# 362MiniProj.net
KiCad netlist of a schematic drawn in EAGLE
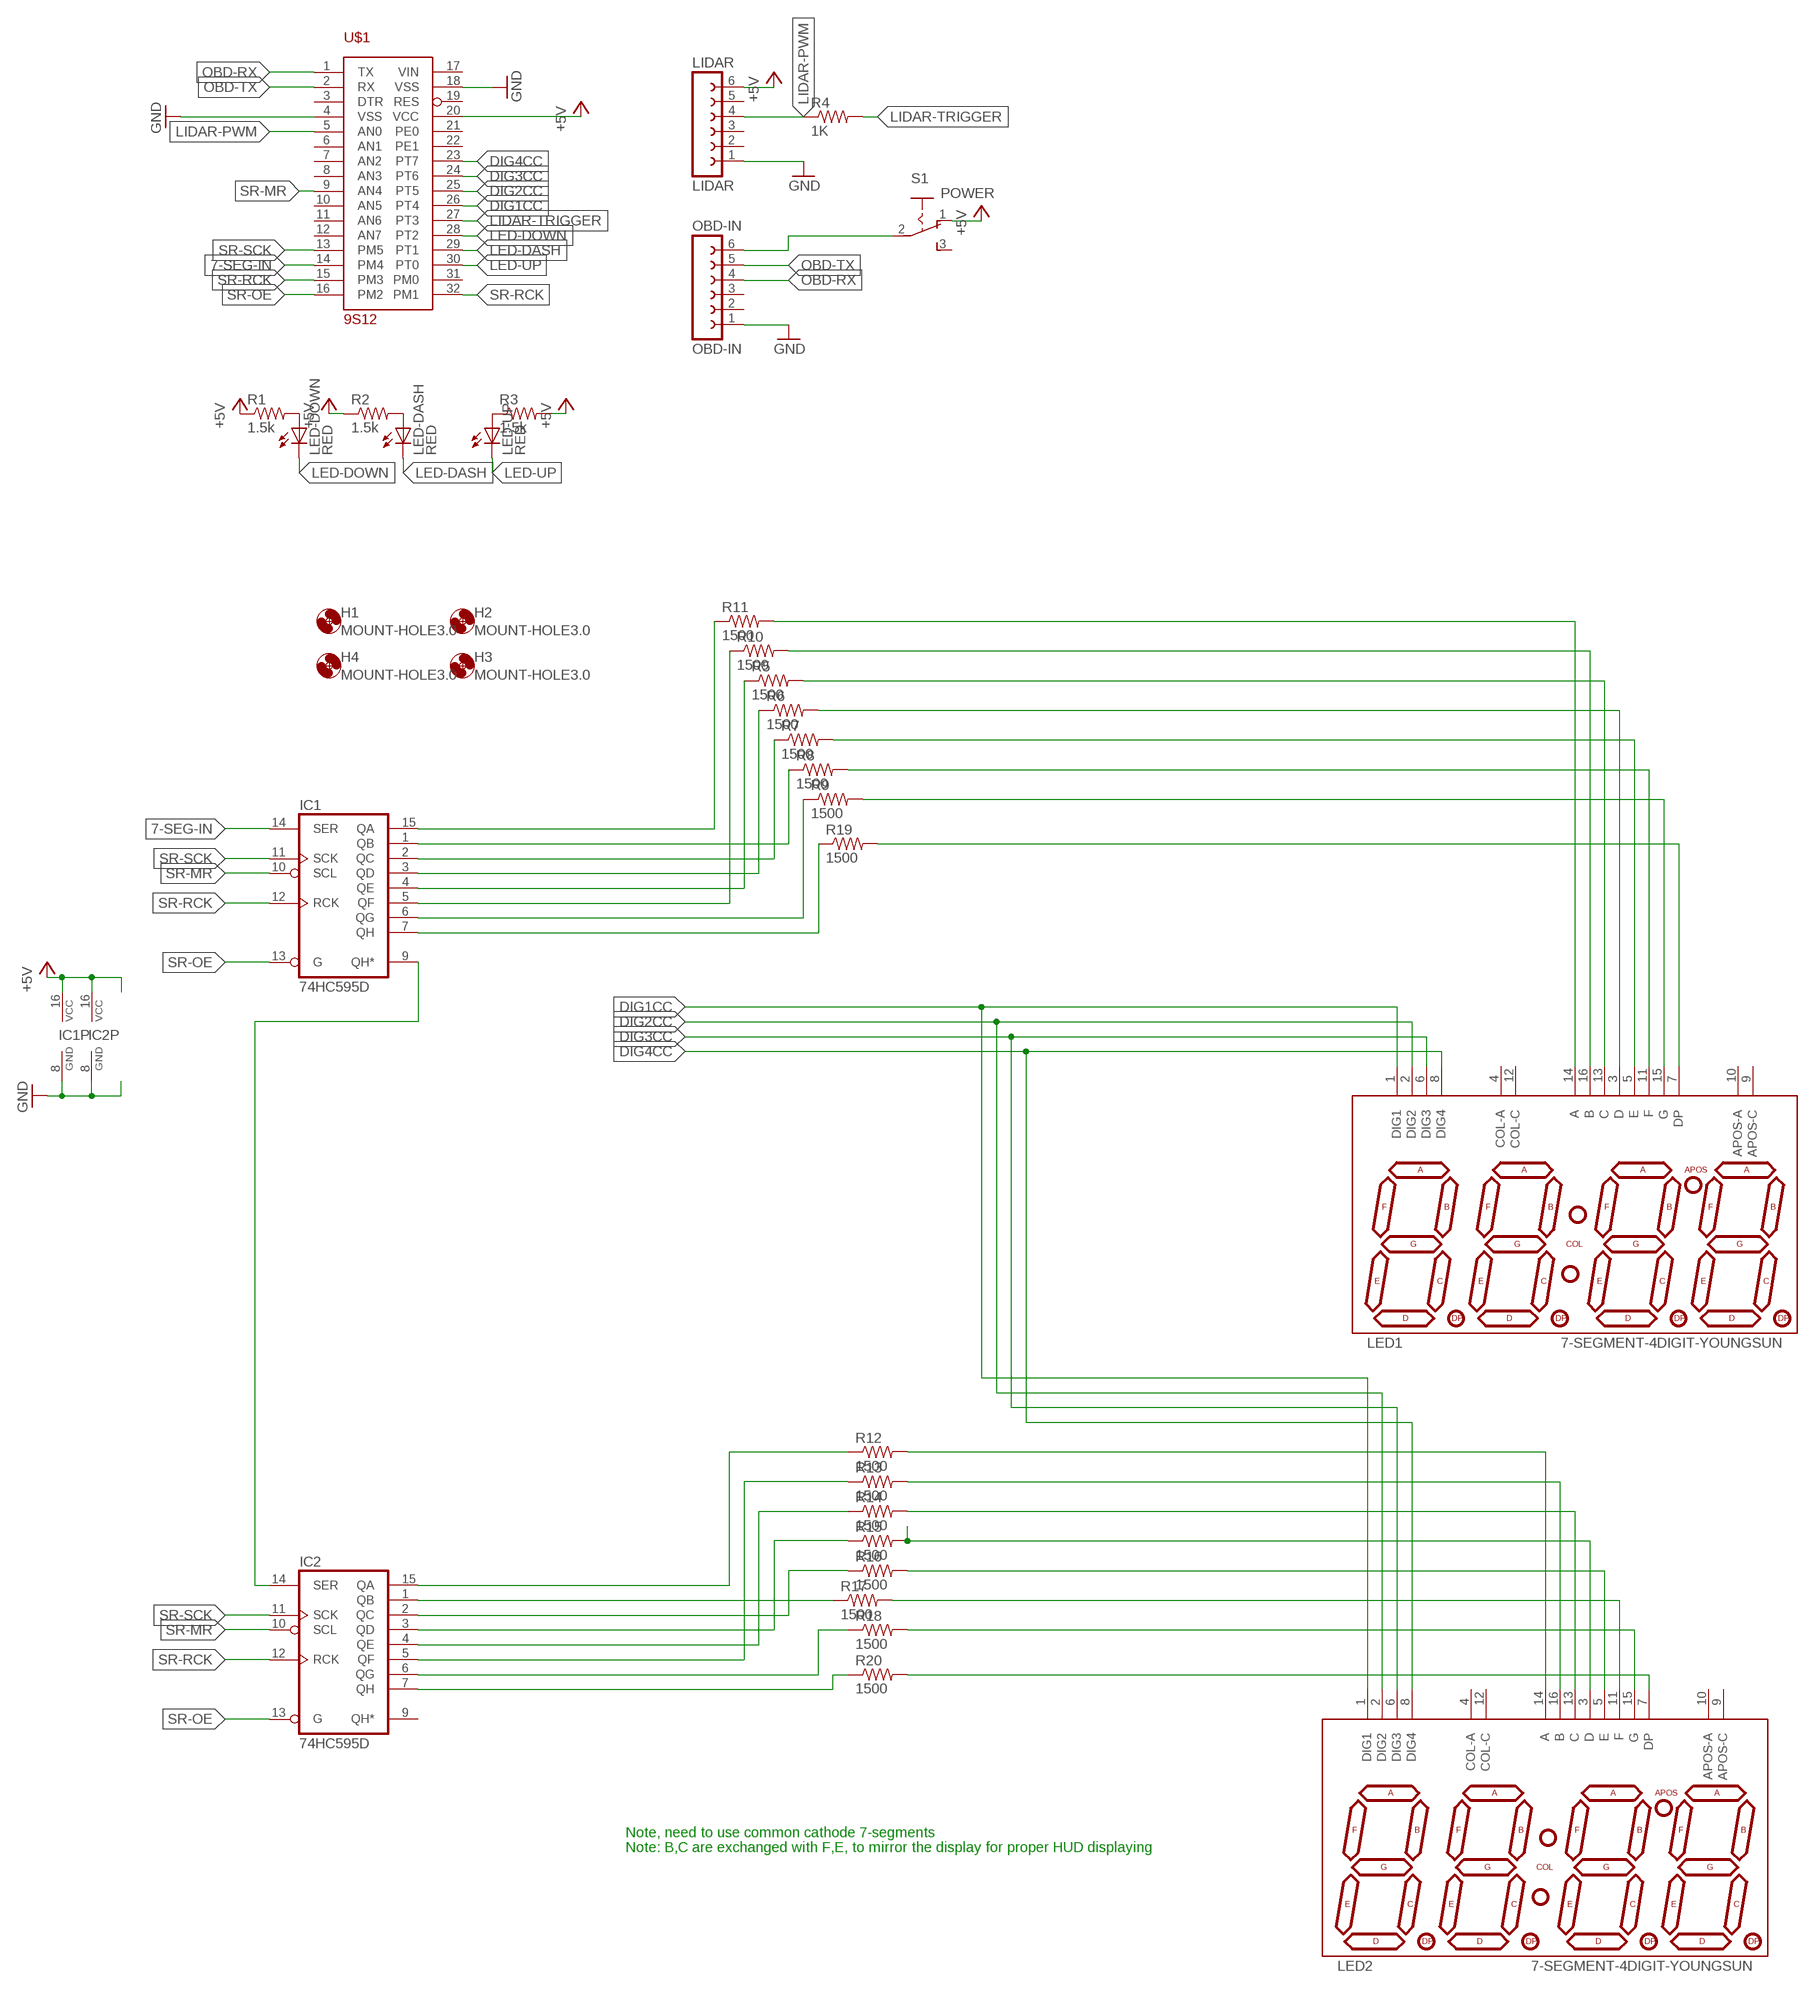
[diagram p0: schematic, sheet 1]

(export (version "E")
  (design (tool "Eeschema 10.0.6"))
  (components
    (comp (ref "H1")
      (value "MOUNT-HOLE3.0")
      (footprint "eagle-import:3,0")
      (libsource (lib "eagle-import") (part "MOUNT-HOLE3.0"))
    )
    (comp (ref "H2")
      (value "MOUNT-HOLE3.0")
      (footprint "eagle-import:3,0")
      (libsource (lib "eagle-import") (part "MOUNT-HOLE3.0"))
    )
    (comp (ref "H3")
      (value "MOUNT-HOLE3.0")
      (footprint "eagle-import:3,0")
      (libsource (lib "eagle-import") (part "MOUNT-HOLE3.0"))
    )
    (comp (ref "H4")
      (value "MOUNT-HOLE3.0")
      (footprint "eagle-import:3,0")
      (libsource (lib "eagle-import") (part "MOUNT-HOLE3.0"))
    )
    (comp (ref "IC1")
      (value "74HC595D")
      (footprint "eagle-import:SO16")
      (libsource (lib "eagle-import") (part "74595DHC"))
    )
    (comp (ref "IC2")
      (value "74HC595D")
      (footprint "eagle-import:SO16")
      (libsource (lib "eagle-import") (part "74595DHC"))
    )
    (comp (ref "LED-DASH")
      (value "RED")
      (footprint "eagle-import:LED_1206")
      (libsource (lib "eagle-import") (part "LED_E"))
    )
    (comp (ref "LED-DOWN")
      (value "RED")
      (footprint "eagle-import:LED_1206")
      (libsource (lib "eagle-import") (part "LED_E"))
    )
    (comp (ref "LED-UP")
      (value "RED")
      (footprint "eagle-import:LED_1206")
      (libsource (lib "eagle-import") (part "LED_E"))
    )
    (comp (ref "LED1")
      (value "7-SEGMENT-4DIGIT-YOUNGSUN")
      (footprint "eagle-import:7-SEGMENT-4DIGIT-YOUNGSUN")
      (libsource (lib "eagle-import") (part "7-SEGMENT-4DIGIT-YOUNGSUN"))
    )
    (comp (ref "LED2")
      (value "7-SEGMENT-4DIGIT-YOUNGSUN")
      (footprint "eagle-import:7-SEGMENT-4DIGIT-YOUNGSUN")
      (libsource (lib "eagle-import") (part "7-SEGMENT-4DIGIT-YOUNGSUN"))
    )
    (comp (ref "LIDAR")
      (value "LIDAR")
      (footprint "eagle-import:FE06")
      (libsource (lib "eagle-import") (part "FE06-1"))
    )
    (comp (ref "OBD-IN")
      (value "OBD-IN")
      (footprint "eagle-import:FE06")
      (libsource (lib "eagle-import") (part "FE06-1"))
    )
    (comp (ref "R1")
      (value "1.5k")
      (footprint "eagle-import:M1206")
      (libsource (lib "eagle-import") (part "R-US_M1206"))
    )
    (comp (ref "R2")
      (value "1.5k")
      (footprint "eagle-import:M1206")
      (libsource (lib "eagle-import") (part "R-US_M1206"))
    )
    (comp (ref "R3")
      (value "1.5k")
      (footprint "eagle-import:M1206")
      (libsource (lib "eagle-import") (part "R-US_M1206"))
    )
    (comp (ref "R4")
      (value "1K")
      (footprint "eagle-import:M1206")
      (libsource (lib "eagle-import") (part "R-US_M1206"))
    )
    (comp (ref "R5")
      (value "1500")
      (footprint "eagle-import:M1206")
      (libsource (lib "eagle-import") (part "R-US_M1206"))
    )
    (comp (ref "R6")
      (value "1500")
      (footprint "eagle-import:M1206")
      (libsource (lib "eagle-import") (part "R-US_M1206"))
    )
    (comp (ref "R7")
      (value "1500")
      (footprint "eagle-import:M1206")
      (libsource (lib "eagle-import") (part "R-US_M1206"))
    )
    (comp (ref "R8")
      (value "1500")
      (footprint "eagle-import:M1206")
      (libsource (lib "eagle-import") (part "R-US_M1206"))
    )
    (comp (ref "R9")
      (value "1500")
      (footprint "eagle-import:M1206")
      (libsource (lib "eagle-import") (part "R-US_M1206"))
    )
    (comp (ref "R10")
      (value "1500")
      (footprint "eagle-import:M1206")
      (libsource (lib "eagle-import") (part "R-US_M1206"))
    )
    (comp (ref "R11")
      (value "1500")
      (footprint "eagle-import:M1206")
      (libsource (lib "eagle-import") (part "R-US_M1206"))
    )
    (comp (ref "R12")
      (value "1500")
      (footprint "eagle-import:M1206")
      (libsource (lib "eagle-import") (part "R-US_M1206"))
    )
    (comp (ref "R13")
      (value "1500")
      (footprint "eagle-import:M1206")
      (libsource (lib "eagle-import") (part "R-US_M1206"))
    )
    (comp (ref "R14")
      (value "1500")
      (footprint "eagle-import:M1206")
      (libsource (lib "eagle-import") (part "R-US_M1206"))
    )
    (comp (ref "R15")
      (value "1500")
      (footprint "eagle-import:M1206")
      (libsource (lib "eagle-import") (part "R-US_M1206"))
    )
    (comp (ref "R16")
      (value "1500")
      (footprint "eagle-import:M1206")
      (libsource (lib "eagle-import") (part "R-US_M1206"))
    )
    (comp (ref "R17")
      (value "1500")
      (footprint "eagle-import:M1206")
      (libsource (lib "eagle-import") (part "R-US_M1206"))
    )
    (comp (ref "R18")
      (value "1500")
      (footprint "eagle-import:M1206")
      (libsource (lib "eagle-import") (part "R-US_M1206"))
    )
    (comp (ref "R19")
      (value "1500")
      (footprint "eagle-import:M1206")
      (libsource (lib "eagle-import") (part "R-US_M1206"))
    )
    (comp (ref "R20")
      (value "1500")
      (footprint "eagle-import:M1206")
      (libsource (lib "eagle-import") (part "R-US_M1206"))
    )
    (comp (ref "S1")
      (value "POWER")
      (footprint "eagle-import:M251")
      (libsource (lib "eagle-import") (part "M251"))
    )
    (comp (ref "U$1")
      (value "9S12")
      (footprint "eagle-import:DIP-32")
      (libsource (lib "eagle-import") (part "9S12"))
    )
  )
  (nets
    (net (code "1") (name "+5V") (class "Default")
      (node (ref "IC1") (pin "16") (pinfunction "VCC_16") (pintype "power_in"))
      (node (ref "IC2") (pin "16") (pinfunction "VCC_16") (pintype "power_in"))
      (node (ref "LIDAR") (pin "6") (pinfunction "6_6") (pintype "passive"))
      (node (ref "R1") (pin "1") (pinfunction "1_1") (pintype "passive"))
      (node (ref "R2") (pin "1") (pinfunction "1_1") (pintype "passive"))
      (node (ref "R3") (pin "2") (pinfunction "2_2") (pintype "passive"))
      (node (ref "S1") (pin "1") (pinfunction "O_1") (pintype "passive"))
      (node (ref "U$1") (pin "20") (pinfunction "VCC_20") (pintype "bidirectional"))
    )
    (net (code "2") (name "7-SEG-IN") (class "Default")
      (node (ref "IC1") (pin "14") (pinfunction "SER_14") (pintype "input"))
      (node (ref "U$1") (pin "14") (pinfunction "PM4_14") (pintype "bidirectional"))
    )
    (net (code "3") (name "DIG1CC") (class "Default")
      (node (ref "LED1") (pin "1") (pinfunction "DIG1_1") (pintype "bidirectional"))
      (node (ref "LED2") (pin "1") (pinfunction "DIG1_1") (pintype "bidirectional"))
      (node (ref "U$1") (pin "26") (pinfunction "PT4_26") (pintype "bidirectional"))
    )
    (net (code "4") (name "DIG2CC") (class "Default")
      (node (ref "LED1") (pin "2") (pinfunction "DIG2_2") (pintype "bidirectional"))
      (node (ref "LED2") (pin "2") (pinfunction "DIG2_2") (pintype "bidirectional"))
      (node (ref "U$1") (pin "25") (pinfunction "PT5_25") (pintype "bidirectional"))
    )
    (net (code "5") (name "DIG3CC") (class "Default")
      (node (ref "LED1") (pin "6") (pinfunction "DIG3_6") (pintype "bidirectional"))
      (node (ref "LED2") (pin "6") (pinfunction "DIG3_6") (pintype "bidirectional"))
      (node (ref "U$1") (pin "24") (pinfunction "PT6_24") (pintype "bidirectional"))
    )
    (net (code "6") (name "DIG4CC") (class "Default")
      (node (ref "LED1") (pin "8") (pinfunction "DIG4_8") (pintype "bidirectional"))
      (node (ref "LED2") (pin "8") (pinfunction "DIG4_8") (pintype "bidirectional"))
      (node (ref "U$1") (pin "23") (pinfunction "PT7_23") (pintype "bidirectional"))
    )
    (net (code "7") (name "GND") (class "Default")
      (node (ref "IC1") (pin "8") (pinfunction "GND_8") (pintype "power_in"))
      (node (ref "IC2") (pin "8") (pinfunction "GND_8") (pintype "power_in"))
      (node (ref "LIDAR") (pin "1") (pinfunction "1_1") (pintype "passive"))
      (node (ref "OBD-IN") (pin "1") (pinfunction "1_1") (pintype "passive"))
      (node (ref "U$1") (pin "18") (pinfunction "VSS_18") (pintype "bidirectional"))
      (node (ref "U$1") (pin "4") (pinfunction "VSS_4") (pintype "bidirectional"))
    )
    (net (code "8") (name "LED-DASH") (class "Default")
      (node (ref "LED-DASH") (pin "C") (pinfunction "C_C") (pintype "passive"))
      (node (ref "U$1") (pin "29") (pinfunction "PT1_29") (pintype "bidirectional"))
    )
    (net (code "9") (name "LED-DOWN") (class "Default")
      (node (ref "LED-DOWN") (pin "C") (pinfunction "C_C") (pintype "passive"))
      (node (ref "U$1") (pin "28") (pinfunction "PT2_28") (pintype "bidirectional"))
    )
    (net (code "10") (name "LED-UP") (class "Default")
      (node (ref "LED-UP") (pin "C") (pinfunction "C_C") (pintype "passive"))
      (node (ref "U$1") (pin "30") (pinfunction "PT0_30") (pintype "bidirectional"))
    )
    (net (code "11") (name "LIDAR-PWM") (class "Default")
      (node (ref "LIDAR") (pin "4") (pinfunction "4_4") (pintype "passive"))
      (node (ref "R4") (pin "1") (pinfunction "1_1") (pintype "passive"))
      (node (ref "U$1") (pin "5") (pinfunction "AN0_5") (pintype "bidirectional"))
    )
    (net (code "12") (name "LIDAR-TRIGGER") (class "Default")
      (node (ref "R4") (pin "2") (pinfunction "2_2") (pintype "passive"))
      (node (ref "U$1") (pin "27") (pinfunction "PT3_27") (pintype "bidirectional"))
    )
    (net (code "13") (name "Net-(IC1A-QA)") (class "Default")
      (node (ref "IC1") (pin "15") (pinfunction "QA_15") (pintype "tri_state"))
      (node (ref "R11") (pin "1") (pinfunction "1_1") (pintype "passive"))
    )
    (net (code "14") (name "Net-(IC1A-QB)") (class "Default")
      (node (ref "IC1") (pin "1") (pinfunction "QB_1") (pintype "tri_state"))
      (node (ref "R8") (pin "1") (pinfunction "1_1") (pintype "passive"))
    )
    (net (code "15") (name "Net-(IC1A-QC)") (class "Default")
      (node (ref "IC1") (pin "2") (pinfunction "QC_2") (pintype "tri_state"))
      (node (ref "R7") (pin "1") (pinfunction "1_1") (pintype "passive"))
    )
    (net (code "16") (name "Net-(IC1A-QD)") (class "Default")
      (node (ref "IC1") (pin "3") (pinfunction "QD_3") (pintype "tri_state"))
      (node (ref "R6") (pin "1") (pinfunction "1_1") (pintype "passive"))
    )
    (net (code "17") (name "Net-(IC1A-QE)") (class "Default")
      (node (ref "IC1") (pin "4") (pinfunction "QE_4") (pintype "tri_state"))
      (node (ref "R5") (pin "1") (pinfunction "1_1") (pintype "passive"))
    )
    (net (code "18") (name "Net-(IC1A-QF)") (class "Default")
      (node (ref "IC1") (pin "5") (pinfunction "QF_5") (pintype "tri_state"))
      (node (ref "R10") (pin "1") (pinfunction "1_1") (pintype "passive"))
    )
    (net (code "19") (name "Net-(IC1A-QG)") (class "Default")
      (node (ref "IC1") (pin "6") (pinfunction "QG_6") (pintype "tri_state"))
      (node (ref "R9") (pin "1") (pinfunction "1_1") (pintype "passive"))
    )
    (net (code "20") (name "Net-(IC1A-QH)") (class "Default")
      (node (ref "IC1") (pin "7") (pinfunction "QH_7") (pintype "tri_state"))
      (node (ref "R19") (pin "1") (pinfunction "1_1") (pintype "passive"))
    )
    (net (code "21") (name "Net-(IC1A-QH*)") (class "Default")
      (node (ref "IC1") (pin "9") (pinfunction "QH*_9") (pintype "tri_state"))
      (node (ref "IC2") (pin "14") (pinfunction "SER_14") (pintype "input"))
    )
    (net (code "22") (name "Net-(IC2A-QA)") (class "Default")
      (node (ref "IC2") (pin "15") (pinfunction "QA_15") (pintype "tri_state"))
      (node (ref "R12") (pin "1") (pinfunction "1_1") (pintype "passive"))
    )
    (net (code "23") (name "Net-(IC2A-QB)") (class "Default")
      (node (ref "IC2") (pin "1") (pinfunction "QB_1") (pintype "tri_state"))
      (node (ref "R17") (pin "1") (pinfunction "1_1") (pintype "passive"))
    )
    (net (code "24") (name "Net-(IC2A-QC)") (class "Default")
      (node (ref "IC2") (pin "2") (pinfunction "QC_2") (pintype "tri_state"))
      (node (ref "R16") (pin "1") (pinfunction "1_1") (pintype "passive"))
    )
    (net (code "25") (name "Net-(IC2A-QD)") (class "Default")
      (node (ref "IC2") (pin "3") (pinfunction "QD_3") (pintype "tri_state"))
      (node (ref "R15") (pin "1") (pinfunction "1_1") (pintype "passive"))
    )
    (net (code "26") (name "Net-(IC2A-QE)") (class "Default")
      (node (ref "IC2") (pin "4") (pinfunction "QE_4") (pintype "tri_state"))
      (node (ref "R14") (pin "1") (pinfunction "1_1") (pintype "passive"))
    )
    (net (code "27") (name "Net-(IC2A-QF)") (class "Default")
      (node (ref "IC2") (pin "5") (pinfunction "QF_5") (pintype "tri_state"))
      (node (ref "R13") (pin "1") (pinfunction "1_1") (pintype "passive"))
    )
    (net (code "28") (name "Net-(IC2A-QG)") (class "Default")
      (node (ref "IC2") (pin "6") (pinfunction "QG_6") (pintype "tri_state"))
      (node (ref "R18") (pin "1") (pinfunction "1_1") (pintype "passive"))
    )
    (net (code "29") (name "Net-(IC2A-QH)") (class "Default")
      (node (ref "IC2") (pin "7") (pinfunction "QH_7") (pintype "tri_state"))
      (node (ref "R20") (pin "1") (pinfunction "1_1") (pintype "passive"))
    )
    (net (code "30") (name "Net-(LED-DASH-PadA)") (class "Default")
      (node (ref "LED-DASH") (pin "A") (pinfunction "A_A") (pintype "passive"))
      (node (ref "R2") (pin "2") (pinfunction "2_2") (pintype "passive"))
    )
    (net (code "31") (name "Net-(LED-DOWN-PadA)") (class "Default")
      (node (ref "LED-DOWN") (pin "A") (pinfunction "A_A") (pintype "passive"))
      (node (ref "R1") (pin "2") (pinfunction "2_2") (pintype "passive"))
    )
    (net (code "32") (name "Net-(LED-UP-PadA)") (class "Default")
      (node (ref "LED-UP") (pin "A") (pinfunction "A_A") (pintype "passive"))
      (node (ref "R3") (pin "1") (pinfunction "1_1") (pintype "passive"))
    )
    (net (code "33") (name "Net-(LED1-A)") (class "Default")
      (node (ref "LED1") (pin "14") (pinfunction "A_14") (pintype "bidirectional"))
      (node (ref "R11") (pin "2") (pinfunction "2_2") (pintype "passive"))
    )
    (net (code "34") (name "Net-(LED1-B)") (class "Default")
      (node (ref "LED1") (pin "16") (pinfunction "B_16") (pintype "bidirectional"))
      (node (ref "R10") (pin "2") (pinfunction "2_2") (pintype "passive"))
    )
    (net (code "35") (name "Net-(LED1-C)") (class "Default")
      (node (ref "LED1") (pin "13") (pinfunction "C_13") (pintype "bidirectional"))
      (node (ref "R5") (pin "2") (pinfunction "2_2") (pintype "passive"))
    )
    (net (code "36") (name "Net-(LED1-D)") (class "Default")
      (node (ref "LED1") (pin "3") (pinfunction "D_3") (pintype "bidirectional"))
      (node (ref "R6") (pin "2") (pinfunction "2_2") (pintype "passive"))
    )
    (net (code "37") (name "Net-(LED1-DP)") (class "Default")
      (node (ref "LED1") (pin "7") (pinfunction "DP_7") (pintype "bidirectional"))
      (node (ref "R19") (pin "2") (pinfunction "2_2") (pintype "passive"))
    )
    (net (code "38") (name "Net-(LED1-E)") (class "Default")
      (node (ref "LED1") (pin "5") (pinfunction "E_5") (pintype "bidirectional"))
      (node (ref "R7") (pin "2") (pinfunction "2_2") (pintype "passive"))
    )
    (net (code "39") (name "Net-(LED1-F)") (class "Default")
      (node (ref "LED1") (pin "11") (pinfunction "F_11") (pintype "bidirectional"))
      (node (ref "R8") (pin "2") (pinfunction "2_2") (pintype "passive"))
    )
    (net (code "40") (name "Net-(LED1-G)") (class "Default")
      (node (ref "LED1") (pin "15") (pinfunction "G_15") (pintype "bidirectional"))
      (node (ref "R9") (pin "2") (pinfunction "2_2") (pintype "passive"))
    )
    (net (code "41") (name "Net-(LED2-A)") (class "Default")
      (node (ref "LED2") (pin "14") (pinfunction "A_14") (pintype "bidirectional"))
      (node (ref "R12") (pin "2") (pinfunction "2_2") (pintype "passive"))
    )
    (net (code "42") (name "Net-(LED2-B)") (class "Default")
      (node (ref "LED2") (pin "16") (pinfunction "B_16") (pintype "bidirectional"))
      (node (ref "R13") (pin "2") (pinfunction "2_2") (pintype "passive"))
    )
    (net (code "43") (name "Net-(LED2-C)") (class "Default")
      (node (ref "LED2") (pin "13") (pinfunction "C_13") (pintype "bidirectional"))
      (node (ref "R14") (pin "2") (pinfunction "2_2") (pintype "passive"))
    )
    (net (code "44") (name "Net-(LED2-D)") (class "Default")
      (node (ref "LED2") (pin "3") (pinfunction "D_3") (pintype "bidirectional"))
      (node (ref "R15") (pin "2") (pinfunction "2_2") (pintype "passive"))
    )
    (net (code "45") (name "Net-(LED2-DP)") (class "Default")
      (node (ref "LED2") (pin "7") (pinfunction "DP_7") (pintype "bidirectional"))
      (node (ref "R20") (pin "2") (pinfunction "2_2") (pintype "passive"))
    )
    (net (code "46") (name "Net-(LED2-E)") (class "Default")
      (node (ref "LED2") (pin "5") (pinfunction "E_5") (pintype "bidirectional"))
      (node (ref "R16") (pin "2") (pinfunction "2_2") (pintype "passive"))
    )
    (net (code "47") (name "Net-(LED2-F)") (class "Default")
      (node (ref "LED2") (pin "11") (pinfunction "F_11") (pintype "bidirectional"))
      (node (ref "R17") (pin "2") (pinfunction "2_2") (pintype "passive"))
    )
    (net (code "48") (name "Net-(LED2-G)") (class "Default")
      (node (ref "LED2") (pin "15") (pinfunction "G_15") (pintype "bidirectional"))
      (node (ref "R18") (pin "2") (pinfunction "2_2") (pintype "passive"))
    )
    (net (code "49") (name "Net-(S1-P)") (class "Default")
      (node (ref "OBD-IN") (pin "6") (pinfunction "6_6") (pintype "passive"))
      (node (ref "S1") (pin "2") (pinfunction "P_2") (pintype "passive"))
    )
    (net (code "50") (name "OBD-RX") (class "Default")
      (node (ref "OBD-IN") (pin "4") (pinfunction "4_4") (pintype "passive"))
      (node (ref "U$1") (pin "1") (pinfunction "TX_1") (pintype "bidirectional"))
    )
    (net (code "51") (name "OBD-TX") (class "Default")
      (node (ref "OBD-IN") (pin "5") (pinfunction "5_5") (pintype "passive"))
      (node (ref "U$1") (pin "2") (pinfunction "RX_2") (pintype "bidirectional"))
    )
    (net (code "52") (name "SR-MR") (class "Default")
      (node (ref "IC1") (pin "10") (pinfunction "SCL_10") (pintype "input"))
      (node (ref "IC2") (pin "10") (pinfunction "SCL_10") (pintype "input"))
      (node (ref "U$1") (pin "9") (pinfunction "AN4_9") (pintype "bidirectional"))
    )
    (net (code "53") (name "SR-OE") (class "Default")
      (node (ref "IC1") (pin "13") (pinfunction "G_13") (pintype "input"))
      (node (ref "IC2") (pin "13") (pinfunction "G_13") (pintype "input"))
      (node (ref "U$1") (pin "16") (pinfunction "PM2_16") (pintype "bidirectional"))
    )
    (net (code "54") (name "SR-RCK") (class "Default")
      (node (ref "IC1") (pin "12") (pinfunction "RCK_12") (pintype "input"))
      (node (ref "IC2") (pin "12") (pinfunction "RCK_12") (pintype "input"))
      (node (ref "U$1") (pin "15") (pinfunction "PM3_15") (pintype "bidirectional"))
      (node (ref "U$1") (pin "32") (pinfunction "PM1_32") (pintype "bidirectional"))
    )
    (net (code "55") (name "SR-SCK") (class "Default")
      (node (ref "IC1") (pin "11") (pinfunction "SCK_11") (pintype "input"))
      (node (ref "IC2") (pin "11") (pinfunction "SCK_11") (pintype "input"))
      (node (ref "U$1") (pin "13") (pinfunction "PM5_13") (pintype "bidirectional"))
    )
    (net (code "56") (name "unconnected-(IC2A-QH*-Pad9)") (class "Default")
      (node (ref "IC2") (pin "9") (pinfunction "QH*_9") (pintype "tri_state"))
    )
    (net (code "57") (name "unconnected-(LED1-APOS-A-Pad10)") (class "Default")
      (node (ref "LED1") (pin "10") (pinfunction "APOS-A_10") (pintype "bidirectional"))
    )
    (net (code "58") (name "unconnected-(LED1-APOS-C-Pad9)") (class "Default")
      (node (ref "LED1") (pin "9") (pinfunction "APOS-C_9") (pintype "bidirectional"))
    )
    (net (code "59") (name "unconnected-(LED1-COL-A-Pad4)") (class "Default")
      (node (ref "LED1") (pin "4") (pinfunction "COL-A_4") (pintype "bidirectional"))
    )
    (net (code "60") (name "unconnected-(LED1-COL-C-Pad12)") (class "Default")
      (node (ref "LED1") (pin "12") (pinfunction "COL-C_12") (pintype "bidirectional"))
    )
    (net (code "61") (name "unconnected-(LED2-APOS-A-Pad10)") (class "Default")
      (node (ref "LED2") (pin "10") (pinfunction "APOS-A_10") (pintype "bidirectional"))
    )
    (net (code "62") (name "unconnected-(LED2-APOS-C-Pad9)") (class "Default")
      (node (ref "LED2") (pin "9") (pinfunction "APOS-C_9") (pintype "bidirectional"))
    )
    (net (code "63") (name "unconnected-(LED2-COL-A-Pad4)") (class "Default")
      (node (ref "LED2") (pin "4") (pinfunction "COL-A_4") (pintype "bidirectional"))
    )
    (net (code "64") (name "unconnected-(LED2-COL-C-Pad12)") (class "Default")
      (node (ref "LED2") (pin "12") (pinfunction "COL-C_12") (pintype "bidirectional"))
    )
    (net (code "65") (name "unconnected-(LIDAR-Pad2)") (class "Default")
      (node (ref "LIDAR") (pin "2") (pinfunction "2_2") (pintype "passive"))
    )
    (net (code "66") (name "unconnected-(LIDAR-Pad3)") (class "Default")
      (node (ref "LIDAR") (pin "3") (pinfunction "3_3") (pintype "passive"))
    )
    (net (code "67") (name "unconnected-(LIDAR-Pad5)") (class "Default")
      (node (ref "LIDAR") (pin "5") (pinfunction "5_5") (pintype "passive"))
    )
    (net (code "68") (name "unconnected-(OBD-IN-Pad2)") (class "Default")
      (node (ref "OBD-IN") (pin "2") (pinfunction "2_2") (pintype "passive"))
    )
    (net (code "69") (name "unconnected-(OBD-IN-Pad3)") (class "Default")
      (node (ref "OBD-IN") (pin "3") (pinfunction "3_3") (pintype "passive"))
    )
    (net (code "70") (name "unconnected-(S1-S-Pad3)") (class "Default")
      (node (ref "S1") (pin "3") (pinfunction "S_3") (pintype "passive"))
    )
    (net (code "71") (name "unconnected-(U$1-AN1-Pad6)") (class "Default")
      (node (ref "U$1") (pin "6") (pinfunction "AN1_6") (pintype "bidirectional"))
    )
    (net (code "72") (name "unconnected-(U$1-AN2-Pad7)") (class "Default")
      (node (ref "U$1") (pin "7") (pinfunction "AN2_7") (pintype "bidirectional"))
    )
    (net (code "73") (name "unconnected-(U$1-AN3-Pad8)") (class "Default")
      (node (ref "U$1") (pin "8") (pinfunction "AN3_8") (pintype "bidirectional"))
    )
    (net (code "74") (name "unconnected-(U$1-AN5-Pad10)") (class "Default")
      (node (ref "U$1") (pin "10") (pinfunction "AN5_10") (pintype "bidirectional"))
    )
    (net (code "75") (name "unconnected-(U$1-AN6-Pad11)") (class "Default")
      (node (ref "U$1") (pin "11") (pinfunction "AN6_11") (pintype "bidirectional"))
    )
    (net (code "76") (name "unconnected-(U$1-AN7-Pad12)") (class "Default")
      (node (ref "U$1") (pin "12") (pinfunction "AN7_12") (pintype "bidirectional"))
    )
    (net (code "77") (name "unconnected-(U$1-DTR-Pad3)") (class "Default")
      (node (ref "U$1") (pin "3") (pinfunction "DTR_3") (pintype "bidirectional"))
    )
    (net (code "78") (name "unconnected-(U$1-PE0-Pad21)") (class "Default")
      (node (ref "U$1") (pin "21") (pinfunction "PE0_21") (pintype "bidirectional"))
    )
    (net (code "79") (name "unconnected-(U$1-PE1-Pad22)") (class "Default")
      (node (ref "U$1") (pin "22") (pinfunction "PE1_22") (pintype "bidirectional"))
    )
    (net (code "80") (name "unconnected-(U$1-PM0-Pad31)") (class "Default")
      (node (ref "U$1") (pin "31") (pinfunction "PM0_31") (pintype "bidirectional"))
    )
    (net (code "81") (name "unconnected-(U$1-RES-Pad19)") (class "Default")
      (node (ref "U$1") (pin "19") (pinfunction "RES_19") (pintype "bidirectional"))
    )
    (net (code "82") (name "unconnected-(U$1-VIN-Pad17)") (class "Default")
      (node (ref "U$1") (pin "17") (pinfunction "VIN_17") (pintype "bidirectional"))
    )
  )
)
